# Breakout_for_ics4343.net
KiCad netlist of a schematic drawn in Altium Designer
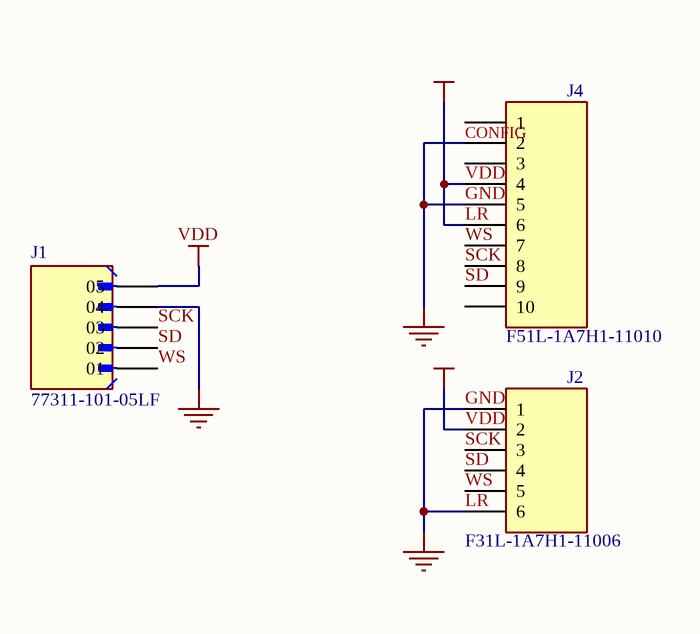
[diagram p0: Breakout_for_ics4343.SchDoc]

(export (version "E")
  (design (tool "Eeschema 10.0.6"))
  (components
    (comp (ref "J1")
      (value "77311-101-05LF")
      (footprint "AMPHENOL_77311-101-05LF")
      (fields (field (name "MF") "Amphenol"))
      (libsource (lib "77311-101-05LF") (part "77311-101-05LF"))
    )
    (comp (ref "J2")
      (value "F31L-1A7H1-11006")
      (footprint "AMPHENOL_F31L-1A7H1-11006")
      (description "Flex Connector, 0.50mm Pitch, Height 2.55mm, Right angle, Flip type, ZIF, 6 position , With MYLAR")
      (fields (field (name "MF") "Amphenol ICC (FCI)"))
      (libsource (lib "F31L-1A7H1-11006") (part "F31L-1A7H1-11006"))
    )
    (comp (ref "J4")
      (value "F51L-1A7H1-11010")
      (footprint "AMPHENOL_F51L-1A7H1-11010")
      (description "Flex Connector, 1.00mm Pitch, Height 2.55mm, Right angle, Flip type, ZIF, 10 position , With MYLAR")
      (fields (field (name "MF") "Amphenol ICC (FCI)"))
      (libsource (lib "F51L-1A7H1-11010") (part "F51L-1A7H1-11010"))
    )
  )
  (nets
    (net (code "1") (name "/SCK") (class "Default")
      (node (ref "J1") (pin "03") (pinfunction "03_03") (pintype "passive"))
      (node (ref "J2") (pin "3") (pinfunction "3_3") (pintype "passive"))
      (node (ref "J4") (pin "8") (pinfunction "8_8") (pintype "passive"))
    )
    (net (code "2") (name "/SD") (class "Default")
      (node (ref "J1") (pin "02") (pinfunction "02_02") (pintype "passive"))
      (node (ref "J2") (pin "4") (pinfunction "4_4") (pintype "passive"))
      (node (ref "J4") (pin "9") (pinfunction "9_9") (pintype "passive"))
    )
    (net (code "3") (name "/WS") (class "Default")
      (node (ref "J1") (pin "01") (pinfunction "01_01") (pintype "passive"))
      (node (ref "J2") (pin "5") (pinfunction "5_5") (pintype "passive"))
      (node (ref "J4") (pin "7") (pinfunction "7_7") (pintype "passive"))
    )
    (net (code "4") (name "GND") (class "Default")
      (node (ref "J1") (pin "04") (pinfunction "04_04") (pintype "passive"))
      (node (ref "J2") (pin "1") (pinfunction "1_1") (pintype "passive"))
      (node (ref "J2") (pin "6") (pinfunction "6_6") (pintype "passive"))
      (node (ref "J4") (pin "2") (pinfunction "2_2") (pintype "passive"))
      (node (ref "J4") (pin "5") (pinfunction "5_5") (pintype "passive"))
    )
    (net (code "5") (name "VDD") (class "Default")
      (node (ref "J1") (pin "05") (pinfunction "05_05") (pintype "passive"))
      (node (ref "J2") (pin "2") (pinfunction "2_2") (pintype "passive"))
      (node (ref "J4") (pin "4") (pinfunction "4_4") (pintype "passive"))
      (node (ref "J4") (pin "6") (pinfunction "6_6") (pintype "passive"))
    )
    (net (code "6") (name "unconnected-(J4-Pad1)") (class "Default")
      (node (ref "J4") (pin "1") (pinfunction "1_1") (pintype "passive"))
    )
    (net (code "7") (name "unconnected-(J4-Pad3)") (class "Default")
      (node (ref "J4") (pin "3") (pinfunction "3_3") (pintype "passive"))
    )
    (net (code "8") (name "unconnected-(J4-Pad10)") (class "Default")
      (node (ref "J4") (pin "10") (pinfunction "10_10") (pintype "passive"))
    )
  )
)
